# top_power.net
KiCad netlist of a schematic drawn in Altium Designer
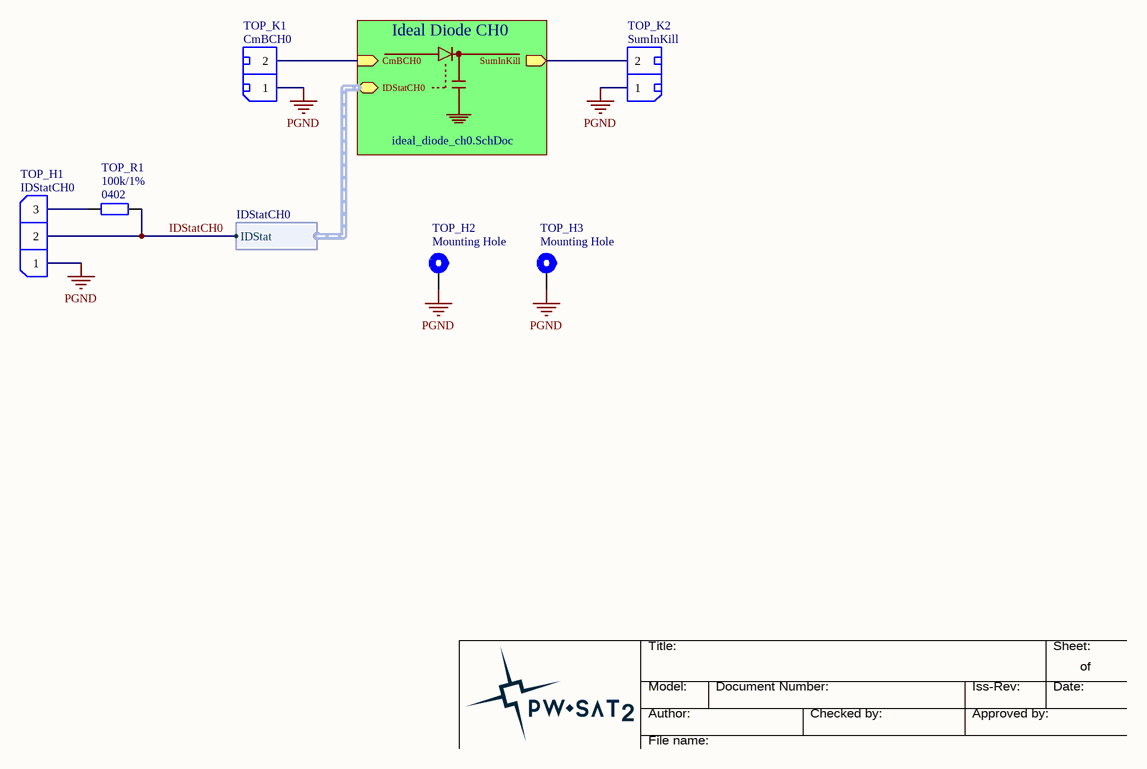
[diagram p0: top_power.SchDoc]

(export (version "E")
  (design (tool "Eeschema 10.0.6"))
  (components
    (comp (ref "TOP_H1")
      (value "IDStatCH0")
      (footprint "Harwin_Datamate_L-Tek_M80-8770305")
      (description "Harwin DataMate L-Tek, 2mm pitch, 1x3pin.")
      (libsource (lib "connectors_printed-circuit-board") (part "Harwin_Datamate_L-Tek_1x3pin"))
    )
    (comp (ref "TOP_H2")
      (value "Mounting Hole")
      (footprint "PC-104_PcbMntHole_M3")
      (description "PCB Mounting Hole")
      (libsource (lib "connectors_printed-circuit-board") (part "MntHole"))
    )
    (comp (ref "TOP_H3")
      (value "Mounting Hole")
      (footprint "PC-104_PcbMntHole_M3")
      (description "PCB Mounting Hole")
      (libsource (lib "connectors_printed-circuit-board") (part "MntHole"))
    )
    (comp (ref "TOP_K1")
      (value "TB-2.5-PD-xx")
      (footprint "TerminalBlock_Spring_2.54_2-R")
      (description "Terminal block with spring, 2-pin, 2.54mm pitch, right angle.")
      (fields (field (name "PROVIDERPARTNUMBER") "CmBCH0") (field (name "PROVIDER") "TME.eu"))
      (libsource (lib "connectors_printed-circuit-board") (part "TerminalBlock_Spring_2.54_2-R"))
    )
    (comp (ref "TOP_K2")
      (value "TB-2.5-PD-xx")
      (footprint "TerminalBlock_Spring_2.54_2-R")
      (description "Terminal block with spring, 2-pin, 2.54mm pitch, right angle.")
      (fields (field (name "PROVIDERPARTNUMBER") "SumInKill") (field (name "PROVIDER") "TME.eu"))
      (libsource (lib "connectors_printed-circuit-board") (part "TerminalBlock_Spring_2.54_2-R"))
    )
    (comp (ref "TOP_R1")
      (value "100k/1%")
      (footprint "SMD_Resistor_0402")
      (description "100k/1% Vishay CRCW 0402 Resistor. 63mW, 100ppm, 50V.")
      (fields (field (name "MANUFACTURER") "Vishay") (field (name "PACKAGE") "0402"))
      (libsource (lib "resistors") (part "CRCW0402100KFKxxxx"))
    )
  )
  (nets
    (net (code "1") (name "/CmBCH0") (class "Default")
      (node (ref "TOP_K1") (pin "2") (pinfunction "2_2") (pintype "passive"))
    )
    (net (code "2") (name "/IDStatCH0") (class "Default")
      (node (ref "TOP_H1") (pin "2") (pinfunction "2_2") (pintype "passive"))
      (node (ref "TOP_R1") (pin "2") (pinfunction "2_2") (pintype "passive"))
    )
    (net (code "3") (name "/SumInKill") (class "Default")
      (node (ref "TOP_K2") (pin "2") (pinfunction "2_2") (pintype "passive"))
    )
    (net (code "5") (name "Net-(TOP_H1-Pad3)") (class "Default")
      (node (ref "TOP_H1") (pin "3") (pinfunction "3_3") (pintype "passive"))
      (node (ref "TOP_R1") (pin "1") (pinfunction "1_1") (pintype "passive"))
    )
    (net (code "6") (name "PGND") (class "Default")
      (node (ref "TOP_H1") (pin "1") (pinfunction "1_1") (pintype "passive"))
      (node (ref "TOP_H2") (pin "1") (pinfunction "1_1") (pintype "passive"))
      (node (ref "TOP_H3") (pin "1") (pinfunction "1_1") (pintype "passive"))
      (node (ref "TOP_K1") (pin "1") (pinfunction "1_1") (pintype "passive"))
      (node (ref "TOP_K2") (pin "1") (pinfunction "1_1") (pintype "passive"))
    )
  )
)
